# RT1064_Power.net
KiCad netlist of a schematic drawn in Altium Designer
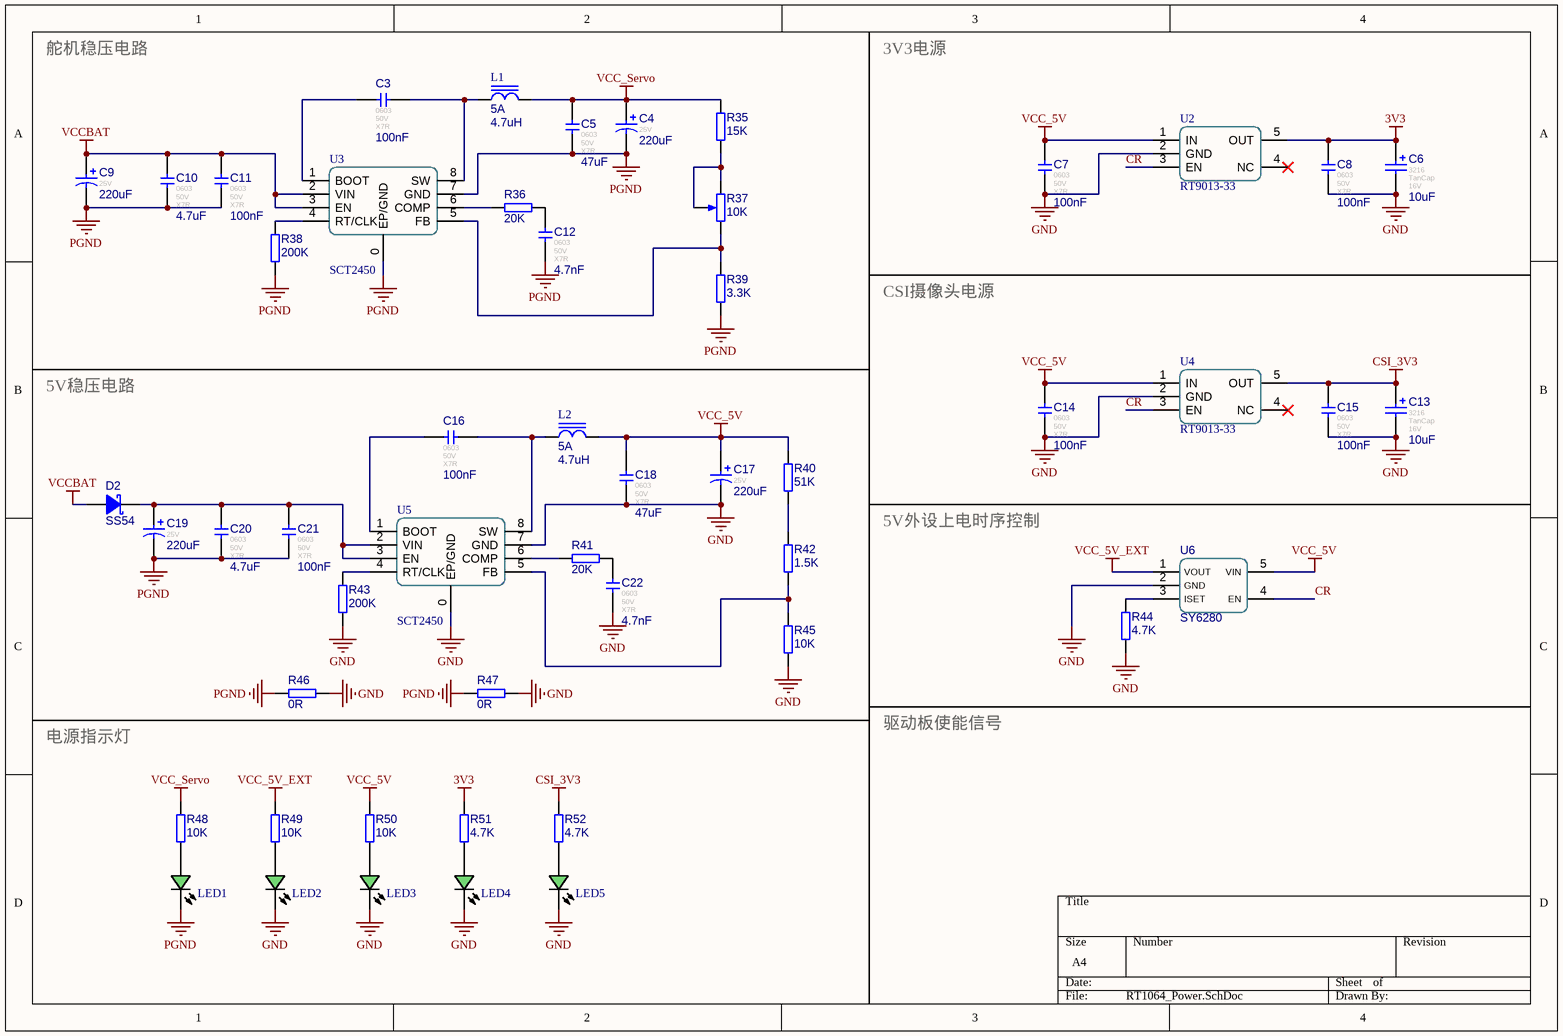
[diagram p0: RT1064_Power.SchDoc]

(export (version "E")
  (design (tool "Eeschema 10.0.6"))
  (components
    (comp (ref "C3")
      (value "100nF")
      (footprint "0603")
      (description "贴片瓷片电容; MLCC; 0603(1608);")
      (fields
        (field (name "VOLTAGE") "50V")
        (field (name "TYPE") "X7R")
        (field (name "Comment") "100nF 50V X7R")
      )
      (libsource (lib "RT1064_V1主板器件封装集成库") (part "100nF 0603 50V X7R"))
    )
    (comp (ref "C4")
      (value "220uF")
      (footprint "CAP-E-S 6.3")
      (description "贴片电解电容 220uF 25V 6.3x7.7")
      (fields (field (name "VOLTAGE") "25V") (field (name "Comment") "220uF 25V 铝电解"))
      (libsource (lib "RT1064_V1主板器件封装集成库") (part "E-S 220uF 25V 6.3x7.7"))
    )
    (comp (ref "C5")
      (value "47uF")
      (footprint "0603")
      (description "贴片瓷片电容; MLCC; 0603(1608);")
      (fields
        (field (name "VOLTAGE") "50V")
        (field (name "TYPE") "X7R")
        (field (name "Comment") "47uF 50V X7R")
      )
      (libsource (lib "RT1064_V1主板器件封装集成库") (part "100nF 0603 50V X7R"))
    )
    (comp (ref "C6")
      (value "10uF")
      (footprint "3216")
      (description "贴片钽电容 10uF 3216 16V")
      (fields
        (field (name "TYPE") "TanCap")
        (field (name "VOLTAGE") "16V")
        (field (name "Comment") "T-S 10uF 3216 16V")
      )
      (libsource (lib "RT1064_V1主板器件封装集成库") (part "T-S 10uF 3216 16V"))
    )
    (comp (ref "C7")
      (value "100nF")
      (footprint "0603")
      (description "贴片瓷片电容; MLCC; 0603(1608);")
      (fields
        (field (name "VOLTAGE") "50V")
        (field (name "TYPE") "X7R")
        (field (name "Comment") "100nF 50V X7R")
      )
      (libsource (lib "RT1064_V1主板器件封装集成库") (part "100nF 0603 50V X7R"))
    )
    (comp (ref "C8")
      (value "100nF")
      (footprint "0603")
      (description "贴片瓷片电容; MLCC; 0603(1608);")
      (fields
        (field (name "VOLTAGE") "50V")
        (field (name "TYPE") "X7R")
        (field (name "Comment") "100nF 50V X7R")
      )
      (libsource (lib "RT1064_V1主板器件封装集成库") (part "100nF 0603 50V X7R"))
    )
    (comp (ref "C9")
      (value "220uF")
      (footprint "CAP-E-S 6.3")
      (description "贴片电解电容 220uF 25V 6.3x7.7")
      (fields (field (name "VOLTAGE") "25V") (field (name "Comment") "220uF 25V 铝电解"))
      (libsource (lib "RT1064_V1主板器件封装集成库") (part "E-S 220uF 25V 6.3x7.7"))
    )
    (comp (ref "C10")
      (value "4.7uF")
      (footprint "0603")
      (description "贴片瓷片电容; MLCC; 0603(1608);")
      (fields
        (field (name "VOLTAGE") "50V")
        (field (name "TYPE") "X7R")
        (field (name "Comment") "4.7uF 50V X7R")
      )
      (libsource (lib "RT1064_V1主板器件封装集成库") (part "100nF 0603 50V X7R"))
    )
    (comp (ref "C11")
      (value "100nF")
      (footprint "0603")
      (description "贴片瓷片电容; MLCC; 0603(1608);")
      (fields
        (field (name "VOLTAGE") "50V")
        (field (name "TYPE") "X7R")
        (field (name "Comment") "100nF 50V X7R")
      )
      (libsource (lib "RT1064_V1主板器件封装集成库") (part "100nF 0603 50V X7R"))
    )
    (comp (ref "C12")
      (value "4.7nF")
      (footprint "0603")
      (description "贴片瓷片电容; MLCC; 0603(1608);")
      (fields
        (field (name "VOLTAGE") "50V")
        (field (name "TYPE") "X7R")
        (field (name "Comment") "4.7nF 50V X7R")
      )
      (libsource (lib "RT1064_V1主板器件封装集成库") (part "4.7nF 0603 50V X7R"))
    )
    (comp (ref "C13")
      (value "10uF")
      (footprint "3216")
      (description "贴片钽电容 10uF 3216 16V")
      (fields
        (field (name "TYPE") "TanCap")
        (field (name "VOLTAGE") "16V")
        (field (name "Comment") "T-S 10uF 3216 16V")
      )
      (libsource (lib "RT1064_V1主板器件封装集成库") (part "T-S 10uF 3216 16V"))
    )
    (comp (ref "C14")
      (value "100nF")
      (footprint "0603")
      (description "贴片瓷片电容; MLCC; 0603(1608);")
      (fields
        (field (name "VOLTAGE") "50V")
        (field (name "TYPE") "X7R")
        (field (name "Comment") "100nF 50V X7R")
      )
      (libsource (lib "RT1064_V1主板器件封装集成库") (part "100nF 0603 50V X7R"))
    )
    (comp (ref "C15")
      (value "100nF")
      (footprint "0603")
      (description "贴片瓷片电容; MLCC; 0603(1608);")
      (fields
        (field (name "VOLTAGE") "50V")
        (field (name "TYPE") "X7R")
        (field (name "Comment") "100nF 50V X7R")
      )
      (libsource (lib "RT1064_V1主板器件封装集成库") (part "100nF 0603 50V X7R"))
    )
    (comp (ref "C16")
      (value "100nF")
      (footprint "0603")
      (description "贴片瓷片电容; MLCC; 0603(1608);")
      (fields
        (field (name "VOLTAGE") "50V")
        (field (name "TYPE") "X7R")
        (field (name "Comment") "100nF 50V X7R")
      )
      (libsource (lib "RT1064_V1主板器件封装集成库") (part "100nF 0603 50V X7R"))
    )
    (comp (ref "C17")
      (value "220uF")
      (footprint "CAP-E-S 6.3")
      (description "贴片电解电容 220uF 25V 6.3x7.7")
      (fields (field (name "VOLTAGE") "25V") (field (name "Comment") "220uF 25V 铝电解"))
      (libsource (lib "RT1064_V1主板器件封装集成库") (part "E-S 220uF 25V 6.3x7.7"))
    )
    (comp (ref "C18")
      (value "47uF")
      (footprint "0603")
      (description "贴片瓷片电容; MLCC; 0603(1608);")
      (fields
        (field (name "VOLTAGE") "50V")
        (field (name "TYPE") "X7R")
        (field (name "Comment") "47uF 50V X7R")
      )
      (libsource (lib "RT1064_V1主板器件封装集成库") (part "100nF 0603 50V X7R"))
    )
    (comp (ref "C19")
      (value "220uF")
      (footprint "CAP-E-S 6.3")
      (description "贴片电解电容 220uF 25V 6.3x7.7")
      (fields (field (name "VOLTAGE") "25V") (field (name "Comment") "220uF 25V 铝电解"))
      (libsource (lib "RT1064_V1主板器件封装集成库") (part "E-S 220uF 25V 6.3x7.7"))
    )
    (comp (ref "C20")
      (value "4.7uF")
      (footprint "0603")
      (description "贴片瓷片电容; MLCC; 0603(1608);")
      (fields
        (field (name "VOLTAGE") "50V")
        (field (name "TYPE") "X7R")
        (field (name "Comment") "4.7uF 50V X7R")
      )
      (libsource (lib "RT1064_V1主板器件封装集成库") (part "100nF 0603 50V X7R"))
    )
    (comp (ref "C21")
      (value "100nF")
      (footprint "0603")
      (description "贴片瓷片电容; MLCC; 0603(1608);")
      (fields
        (field (name "VOLTAGE") "50V")
        (field (name "TYPE") "X7R")
        (field (name "Comment") "100nF 50V X7R")
      )
      (libsource (lib "RT1064_V1主板器件封装集成库") (part "100nF 0603 50V X7R"))
    )
    (comp (ref "C22")
      (value "4.7nF")
      (footprint "0603")
      (description "贴片瓷片电容; MLCC; 0603(1608);")
      (fields
        (field (name "VOLTAGE") "50V")
        (field (name "TYPE") "X7R")
        (field (name "Comment") "4.7nF 50V X7R")
      )
      (libsource (lib "RT1064_V1主板器件封装集成库") (part "4.7nF 0603 50V X7R"))
    )
    (comp (ref "D2")
      (value "SS54")
      (footprint "SMA-L[DO-214AC]")
      (description "SS54 肖特基二极管")
      (libsource (lib "RT1064_V1主板器件封装集成库") (part "SS54"))
    )
    (comp (ref "L1")
      (value "4.7uH")
      (footprint "0630 TPC 7*7*3")
      (description "功率电感")
      (fields
        (field (name "IMAX") "5A")
        (field (name "Comment") "4.7uH 5A")
        (field (name "PUBLISHER") "Altium Limited")
      )
      (libsource (lib "RT1064_V1主板器件封装集成库") (part "Ind-Power"))
    )
    (comp (ref "L2")
      (value "4.7uH")
      (footprint "0630 TPC 7*7*3")
      (description "功率电感")
      (fields
        (field (name "IMAX") "5A")
        (field (name "Comment") "4.7uH 5A")
        (field (name "PUBLISHER") "Altium Limited")
      )
      (libsource (lib "RT1064_V1主板器件封装集成库") (part "Ind-Power"))
    )
    (comp (ref "LED1")
      (value "翠绿贴片LED")
      (footprint "LEDC1608(0603)-L")
      (fields (field (name "PUBLISHER") "Altium Limited"))
      (libsource (lib "RT1064_V1主板器件封装集成库") (part "LED Chip Green"))
    )
    (comp (ref "LED2")
      (value "翠绿贴片LED")
      (footprint "LEDC1608(0603)-L")
      (fields (field (name "PUBLISHER") "Altium Limited"))
      (libsource (lib "RT1064_V1主板器件封装集成库") (part "LED Chip Green"))
    )
    (comp (ref "LED3")
      (value "翠绿贴片LED")
      (footprint "LEDC1608(0603)-L")
      (fields (field (name "PUBLISHER") "Altium Limited"))
      (libsource (lib "RT1064_V1主板器件封装集成库") (part "LED Chip Green"))
    )
    (comp (ref "LED4")
      (value "翠绿贴片LED")
      (footprint "LEDC1608(0603)-L")
      (fields (field (name "PUBLISHER") "Altium Limited"))
      (libsource (lib "RT1064_V1主板器件封装集成库") (part "LED Chip Green"))
    )
    (comp (ref "LED5")
      (value "翠绿贴片LED")
      (footprint "LEDC1608(0603)-L")
      (fields (field (name "PUBLISHER") "Altium Limited"))
      (libsource (lib "RT1064_V1主板器件封装集成库") (part "LED Chip Green"))
    )
    (comp (ref "R35")
      (value "15K")
      (footprint "RESC1608[0603]S-L")
      (description "贴片电阻")
      (fields (field (name "POWER") "1/8W") (field (name "TOLERANCE") "±1%"))
      (libsource (lib "RT1064_V1主板器件封装集成库") (part "Res-Chip"))
    )
    (comp (ref "R36")
      (value "20K")
      (footprint "RESC1608[0603]S-L")
      (description "贴片电阻")
      (fields (field (name "POWER") "1/8W") (field (name "TOLERANCE") "±1%"))
      (libsource (lib "RT1064_V1主板器件封装集成库") (part "Res-Chip"))
    )
    (comp (ref "R37")
      (value "10K")
      (footprint "RESPOT3296W")
      (description "可调电阻")
      (libsource (lib "RT1064_V1主板器件封装集成库") (part "Res-Adj-3p"))
    )
    (comp (ref "R38")
      (value "200K")
      (footprint "RESC1608[0603]S-L")
      (description "贴片电阻")
      (fields (field (name "POWER") "1/8W") (field (name "TOLERANCE") "±1%"))
      (libsource (lib "RT1064_V1主板器件封装集成库") (part "Res-Chip"))
    )
    (comp (ref "R39")
      (value "3.3K")
      (footprint "RESC1608[0603]S-L")
      (description "贴片电阻")
      (fields (field (name "POWER") "1/8W") (field (name "TOLERANCE") "±1%"))
      (libsource (lib "RT1064_V1主板器件封装集成库") (part "Res-Chip"))
    )
    (comp (ref "R40")
      (value "51K")
      (footprint "RESC1608[0603]S-L")
      (description "贴片电阻")
      (fields (field (name "POWER") "1/8W") (field (name "TOLERANCE") "±1%"))
      (libsource (lib "RT1064_V1主板器件封装集成库") (part "Res-Chip"))
    )
    (comp (ref "R41")
      (value "20K")
      (footprint "RESC1608[0603]S-L")
      (description "贴片电阻")
      (fields (field (name "POWER") "1/8W") (field (name "TOLERANCE") "±1%"))
      (libsource (lib "RT1064_V1主板器件封装集成库") (part "Res-Chip"))
    )
    (comp (ref "R42")
      (value "1.5K")
      (footprint "RESC1608[0603]S-L")
      (description "贴片电阻")
      (fields (field (name "POWER") "1/8W") (field (name "TOLERANCE") "±1%"))
      (libsource (lib "RT1064_V1主板器件封装集成库") (part "Res-Chip"))
    )
    (comp (ref "R43")
      (value "200K")
      (footprint "RESC1608[0603]S-L")
      (description "贴片电阻")
      (fields (field (name "POWER") "1/8W") (field (name "TOLERANCE") "±1%"))
      (libsource (lib "RT1064_V1主板器件封装集成库") (part "Res-Chip"))
    )
    (comp (ref "R44")
      (value "4.7K")
      (footprint "RESC1608[0603]S-L")
      (description "贴片电阻")
      (fields (field (name "POWER") "1/8W") (field (name "TOLERANCE") "±1%"))
      (libsource (lib "RT1064_V1主板器件封装集成库") (part "Res-Chip"))
    )
    (comp (ref "R45")
      (value "10K")
      (footprint "RESC1608[0603]S-L")
      (description "贴片电阻")
      (fields (field (name "POWER") "1/8W") (field (name "TOLERANCE") "±1%"))
      (libsource (lib "RT1064_V1主板器件封装集成库") (part "Res-Chip"))
    )
    (comp (ref "R46")
      (value "0R")
      (footprint "RESC1608[0603]S-L")
      (description "贴片电阻")
      (fields (field (name "POWER") "1/8W") (field (name "TOLERANCE") "±1%"))
      (libsource (lib "RT1064_V1主板器件封装集成库") (part "Res-Chip_1"))
    )
    (comp (ref "R47")
      (value "0R")
      (footprint "RESC1608[0603]S-L")
      (description "贴片电阻")
      (fields (field (name "POWER") "1/8W") (field (name "TOLERANCE") "±1%"))
      (libsource (lib "RT1064_V1主板器件封装集成库") (part "Res-Chip_1"))
    )
    (comp (ref "R48")
      (value "10K")
      (footprint "RESC1608[0603]S-L")
      (description "贴片电阻")
      (fields (field (name "POWER") "1/8W") (field (name "TOLERANCE") "±1%"))
      (libsource (lib "RT1064_V1主板器件封装集成库") (part "Res-Chip"))
    )
    (comp (ref "R49")
      (value "10K")
      (footprint "RESC1608[0603]S-L")
      (description "贴片电阻")
      (fields (field (name "POWER") "1/8W") (field (name "TOLERANCE") "±1%"))
      (libsource (lib "RT1064_V1主板器件封装集成库") (part "Res-Chip"))
    )
    (comp (ref "R50")
      (value "10K")
      (footprint "RESC1608[0603]S-L")
      (description "贴片电阻")
      (fields (field (name "POWER") "1/8W") (field (name "TOLERANCE") "±1%"))
      (libsource (lib "RT1064_V1主板器件封装集成库") (part "Res-Chip"))
    )
    (comp (ref "R51")
      (value "4.7K")
      (footprint "RESC1608[0603]S-L")
      (description "贴片电阻")
      (fields (field (name "POWER") "1/8W") (field (name "TOLERANCE") "±1%"))
      (libsource (lib "RT1064_V1主板器件封装集成库") (part "Res-Chip"))
    )
    (comp (ref "R52")
      (value "4.7K")
      (footprint "RESC1608[0603]S-L")
      (description "贴片电阻")
      (fields (field (name "POWER") "1/8W") (field (name "TOLERANCE") "±1%"))
      (libsource (lib "RT1064_V1主板器件封装集成库") (part "Res-Chip"))
    )
    (comp (ref "U2")
      (value "RT9013-33")
      (footprint "SOT-23-5")
      (description "3.3V 500mA SOT-23-5 LDO")
      (libsource (lib "RT1064_V1主板器件封装集成库") (part "RT9013-33"))
    )
    (comp (ref "U3")
      (value "SCT2450")
      (footprint "SOP-8E")
      (libsource (lib "RT1064_V1主板器件封装集成库") (part "SCT2450"))
    )
    (comp (ref "U4")
      (value "RT9013-33")
      (footprint "SOT-23-5")
      (description "3.3V 500mA SOT-23-5 LDO")
      (libsource (lib "RT1064_V1主板器件封装集成库") (part "RT9013-33"))
    )
    (comp (ref "U5")
      (value "SCT2450")
      (footprint "SOP-8E")
      (libsource (lib "RT1064_V1主板器件封装集成库") (part "SCT2450"))
    )
    (comp (ref "U6")
      (value "SY6280")
      (footprint "SOT-23-5")
      (description "SY6280 2A 限额配电开关")
      (libsource (lib "RT1064_V1主板器件封装集成库") (part "SY6280"))
    )
  )
  (nets
    (net (code "1") (name "/CR") (class "Default")
      (node (ref "U2") (pin "3") (pinfunction "EN_3") (pintype "passive"))
      (node (ref "U4") (pin "3") (pinfunction "EN_3") (pintype "passive"))
      (node (ref "U6") (pin "4") (pinfunction "EN_4") (pintype "passive"))
    )
    (net (code "2") (name "3V3") (class "Default")
      (node (ref "C6") (pin "1") (pinfunction "1_1") (pintype "passive"))
      (node (ref "C8") (pin "2") (pinfunction "2_2") (pintype "passive"))
      (node (ref "R51") (pin "2") (pinfunction "2_2") (pintype "passive"))
      (node (ref "U2") (pin "5") (pinfunction "OUT_5") (pintype "passive"))
    )
    (net (code "3") (name "CSI_3V3") (class "Default")
      (node (ref "C13") (pin "1") (pinfunction "1_1") (pintype "passive"))
      (node (ref "C15") (pin "2") (pinfunction "2_2") (pintype "passive"))
      (node (ref "R52") (pin "2") (pinfunction "2_2") (pintype "passive"))
      (node (ref "U4") (pin "5") (pinfunction "OUT_5") (pintype "passive"))
    )
    (net (code "4") (name "GND") (class "Default")
      (node (ref "C13") (pin "2") (pinfunction "2_2") (pintype "passive"))
      (node (ref "C14") (pin "1") (pinfunction "1_1") (pintype "passive"))
      (node (ref "C15") (pin "1") (pinfunction "1_1") (pintype "passive"))
      (node (ref "C17") (pin "2") (pinfunction "2_2") (pintype "passive"))
      (node (ref "C18") (pin "1") (pinfunction "1_1") (pintype "passive"))
      (node (ref "C22") (pin "1") (pinfunction "1_1") (pintype "passive"))
      (node (ref "C6") (pin "2") (pinfunction "2_2") (pintype "passive"))
      (node (ref "C7") (pin "1") (pinfunction "1_1") (pintype "passive"))
      (node (ref "C8") (pin "1") (pinfunction "1_1") (pintype "passive"))
      (node (ref "LED2") (pin "C") (pinfunction "C_C") (pintype "passive"))
      (node (ref "LED3") (pin "C") (pinfunction "C_C") (pintype "passive"))
      (node (ref "LED4") (pin "C") (pinfunction "C_C") (pintype "passive"))
      (node (ref "LED5") (pin "C") (pinfunction "C_C") (pintype "passive"))
      (node (ref "R43") (pin "1") (pinfunction "1_1") (pintype "passive"))
      (node (ref "R44") (pin "1") (pinfunction "1_1") (pintype "passive"))
      (node (ref "R45") (pin "1") (pinfunction "1_1") (pintype "passive"))
      (node (ref "R46") (pin "2") (pinfunction "2_2") (pintype "passive"))
      (node (ref "R47") (pin "2") (pinfunction "2_2") (pintype "passive"))
      (node (ref "U2") (pin "2") (pinfunction "GND_2") (pintype "passive"))
      (node (ref "U4") (pin "2") (pinfunction "GND_2") (pintype "passive"))
      (node (ref "U5") (pin "0") (pinfunction "EP/GND_0") (pintype "passive"))
      (node (ref "U5") (pin "7") (pinfunction "GND_7") (pintype "passive"))
      (node (ref "U6") (pin "2") (pinfunction "GND_2") (pintype "passive"))
    )
    (net (code "5") (name "Net-(C12-Pad2)") (class "Default")
      (node (ref "C12") (pin "2") (pinfunction "2_2") (pintype "passive"))
      (node (ref "R36") (pin "1") (pinfunction "1_1") (pintype "passive"))
    )
    (net (code "6") (name "Net-(C22-Pad2)") (class "Default")
      (node (ref "C22") (pin "2") (pinfunction "2_2") (pintype "passive"))
      (node (ref "R41") (pin "1") (pinfunction "1_1") (pintype "passive"))
    )
    (net (code "7") (name "Net-(LED1-PadA)") (class "Default")
      (node (ref "LED1") (pin "A") (pinfunction "A_A") (pintype "passive"))
      (node (ref "R48") (pin "1") (pinfunction "1_1") (pintype "passive"))
    )
    (net (code "8") (name "Net-(LED2-PadA)") (class "Default")
      (node (ref "LED2") (pin "A") (pinfunction "A_A") (pintype "passive"))
      (node (ref "R49") (pin "1") (pinfunction "1_1") (pintype "passive"))
    )
    (net (code "9") (name "Net-(LED3-PadA)") (class "Default")
      (node (ref "LED3") (pin "A") (pinfunction "A_A") (pintype "passive"))
      (node (ref "R50") (pin "1") (pinfunction "1_1") (pintype "passive"))
    )
    (net (code "10") (name "Net-(LED4-PadA)") (class "Default")
      (node (ref "LED4") (pin "A") (pinfunction "A_A") (pintype "passive"))
      (node (ref "R51") (pin "1") (pinfunction "1_1") (pintype "passive"))
    )
    (net (code "11") (name "Net-(LED5-PadA)") (class "Default")
      (node (ref "LED5") (pin "A") (pinfunction "A_A") (pintype "passive"))
      (node (ref "R52") (pin "1") (pinfunction "1_1") (pintype "passive"))
    )
    (net (code "12") (name "Net-(R37-BOT)") (class "Default")
      (node (ref "R37") (pin "2") (pinfunction "BOT_2") (pintype "passive"))
      (node (ref "R39") (pin "2") (pinfunction "2_2") (pintype "passive"))
      (node (ref "U3") (pin "5") (pinfunction "FB_5") (pintype "passive"))
    )
    (net (code "13") (name "Net-(R37-TOP)") (class "Default")
      (node (ref "R35") (pin "1") (pinfunction "1_1") (pintype "passive"))
      (node (ref "R37") (pin "1") (pinfunction "TOP_1") (pintype "passive"))
      (node (ref "R37") (pin "ADJ") (pinfunction "ADJ_ADJ") (pintype "passive"))
    )
    (net (code "14") (name "Net-(R40-Pad1)") (class "Default")
      (node (ref "R40") (pin "1") (pinfunction "1_1") (pintype "passive"))
      (node (ref "R42") (pin "2") (pinfunction "2_2") (pintype "passive"))
    )
    (net (code "15") (name "Net-(U3-BOOT)") (class "Default")
      (node (ref "C3") (pin "2") (pinfunction "2_2") (pintype "passive"))
      (node (ref "U3") (pin "1") (pinfunction "BOOT_1") (pintype "passive"))
    )
    (net (code "16") (name "Net-(U3-COMP)") (class "Default")
      (node (ref "R36") (pin "2") (pinfunction "2_2") (pintype "passive"))
      (node (ref "U3") (pin "6") (pinfunction "COMP_6") (pintype "passive"))
    )
    (net (code "17") (name "Net-(U3-RT{slash}CLK)") (class "Default")
      (node (ref "R38") (pin "2") (pinfunction "2_2") (pintype "passive"))
      (node (ref "U3") (pin "4") (pinfunction "RT/CLK_4") (pintype "passive"))
    )
    (net (code "18") (name "Net-(U3-SW)") (class "Default")
      (node (ref "C3") (pin "1") (pinfunction "1_1") (pintype "passive"))
      (node (ref "L1") (pin "1") (pinfunction "1_1") (pintype "passive"))
      (node (ref "U3") (pin "8") (pinfunction "SW_8") (pintype "passive"))
    )
    (net (code "19") (name "Net-(U5-BOOT)") (class "Default")
      (node (ref "C16") (pin "2") (pinfunction "2_2") (pintype "passive"))
      (node (ref "U5") (pin "1") (pinfunction "BOOT_1") (pintype "passive"))
    )
    (net (code "20") (name "Net-(U5-COMP)") (class "Default")
      (node (ref "R41") (pin "2") (pinfunction "2_2") (pintype "passive"))
      (node (ref "U5") (pin "6") (pinfunction "COMP_6") (pintype "passive"))
    )
    (net (code "21") (name "Net-(U5-EN)") (class "Default")
      (node (ref "C19") (pin "1") (pinfunction "1_1") (pintype "passive"))
      (node (ref "C20") (pin "2") (pinfunction "2_2") (pintype "passive"))
      (node (ref "C21") (pin "2") (pinfunction "2_2") (pintype "passive"))
      (node (ref "D2") (pin "K") (pinfunction "K_K") (pintype "passive"))
      (node (ref "U5") (pin "2") (pinfunction "VIN_2") (pintype "passive"))
      (node (ref "U5") (pin "3") (pinfunction "EN_3") (pintype "passive"))
    )
    (net (code "22") (name "Net-(U5-FB)") (class "Default")
      (node (ref "R42") (pin "1") (pinfunction "1_1") (pintype "passive"))
      (node (ref "R45") (pin "2") (pinfunction "2_2") (pintype "passive"))
      (node (ref "U5") (pin "5") (pinfunction "FB_5") (pintype "passive"))
    )
    (net (code "23") (name "Net-(U5-RT{slash}CLK)") (class "Default")
      (node (ref "R43") (pin "2") (pinfunction "2_2") (pintype "passive"))
      (node (ref "U5") (pin "4") (pinfunction "RT/CLK_4") (pintype "passive"))
    )
    (net (code "24") (name "Net-(U5-SW)") (class "Default")
      (node (ref "C16") (pin "1") (pinfunction "1_1") (pintype "passive"))
      (node (ref "L2") (pin "1") (pinfunction "1_1") (pintype "passive"))
      (node (ref "U5") (pin "8") (pinfunction "SW_8") (pintype "passive"))
    )
    (net (code "25") (name "Net-(U6-ISET)") (class "Default")
      (node (ref "R44") (pin "2") (pinfunction "2_2") (pintype "passive"))
      (node (ref "U6") (pin "3") (pinfunction "ISET_3") (pintype "passive"))
    )
    (net (code "26") (name "PGND") (class "Default")
      (node (ref "C10") (pin "1") (pinfunction "1_1") (pintype "passive"))
      (node (ref "C11") (pin "1") (pinfunction "1_1") (pintype "passive"))
      (node (ref "C12") (pin "1") (pinfunction "1_1") (pintype "passive"))
      (node (ref "C19") (pin "2") (pinfunction "2_2") (pintype "passive"))
      (node (ref "C20") (pin "1") (pinfunction "1_1") (pintype "passive"))
      (node (ref "C21") (pin "1") (pinfunction "1_1") (pintype "passive"))
      (node (ref "C4") (pin "2") (pinfunction "2_2") (pintype "passive"))
      (node (ref "C5") (pin "1") (pinfunction "1_1") (pintype "passive"))
      (node (ref "C9") (pin "2") (pinfunction "2_2") (pintype "passive"))
      (node (ref "LED1") (pin "C") (pinfunction "C_C") (pintype "passive"))
      (node (ref "R38") (pin "1") (pinfunction "1_1") (pintype "passive"))
      (node (ref "R39") (pin "1") (pinfunction "1_1") (pintype "passive"))
      (node (ref "R46") (pin "1") (pinfunction "1_1") (pintype "passive"))
      (node (ref "R47") (pin "1") (pinfunction "1_1") (pintype "passive"))
      (node (ref "U3") (pin "0") (pinfunction "EP/GND_0") (pintype "passive"))
      (node (ref "U3") (pin "7") (pinfunction "GND_7") (pintype "passive"))
    )
    (net (code "27") (name "VCCBAT") (class "Default")
      (node (ref "C10") (pin "2") (pinfunction "2_2") (pintype "passive"))
      (node (ref "C11") (pin "2") (pinfunction "2_2") (pintype "passive"))
      (node (ref "C9") (pin "1") (pinfunction "1_1") (pintype "passive"))
      (node (ref "D2") (pin "A") (pinfunction "A_A") (pintype "passive"))
      (node (ref "U3") (pin "2") (pinfunction "VIN_2") (pintype "passive"))
      (node (ref "U3") (pin "3") (pinfunction "EN_3") (pintype "passive"))
    )
    (net (code "28") (name "VCC_5V") (class "Default")
      (node (ref "C14") (pin "2") (pinfunction "2_2") (pintype "passive"))
      (node (ref "C17") (pin "1") (pinfunction "1_1") (pintype "passive"))
      (node (ref "C18") (pin "2") (pinfunction "2_2") (pintype "passive"))
      (node (ref "C7") (pin "2") (pinfunction "2_2") (pintype "passive"))
      (node (ref "L2") (pin "2") (pinfunction "2_2") (pintype "passive"))
      (node (ref "R40") (pin "2") (pinfunction "2_2") (pintype "passive"))
      (node (ref "R50") (pin "2") (pinfunction "2_2") (pintype "passive"))
      (node (ref "U2") (pin "1") (pinfunction "IN_1") (pintype "passive"))
      (node (ref "U4") (pin "1") (pinfunction "IN_1") (pintype "passive"))
      (node (ref "U6") (pin "5") (pinfunction "VIN_5") (pintype "passive"))
    )
    (net (code "29") (name "VCC_5V_EXT") (class "Default")
      (node (ref "R49") (pin "2") (pinfunction "2_2") (pintype "passive"))
      (node (ref "U6") (pin "1") (pinfunction "VOUT_1") (pintype "passive"))
    )
    (net (code "30") (name "VCC_Servo") (class "Default")
      (node (ref "C4") (pin "1") (pinfunction "1_1") (pintype "passive"))
      (node (ref "C5") (pin "2") (pinfunction "2_2") (pintype "passive"))
      (node (ref "L1") (pin "2") (pinfunction "2_2") (pintype "passive"))
      (node (ref "R35") (pin "2") (pinfunction "2_2") (pintype "passive"))
      (node (ref "R48") (pin "2") (pinfunction "2_2") (pintype "passive"))
    )
    (net (code "31") (name "unconnected-(U2-NC-Pad4)") (class "Default")
      (node (ref "U2") (pin "4") (pinfunction "NC_4") (pintype "passive+no_connect"))
    )
    (net (code "32") (name "unconnected-(U4-NC-Pad4)") (class "Default")
      (node (ref "U4") (pin "4") (pinfunction "NC_4") (pintype "passive+no_connect"))
    )
  )
)
